# CarrierConnector.net
KiCad netlist of a schematic drawn in Altium Designer
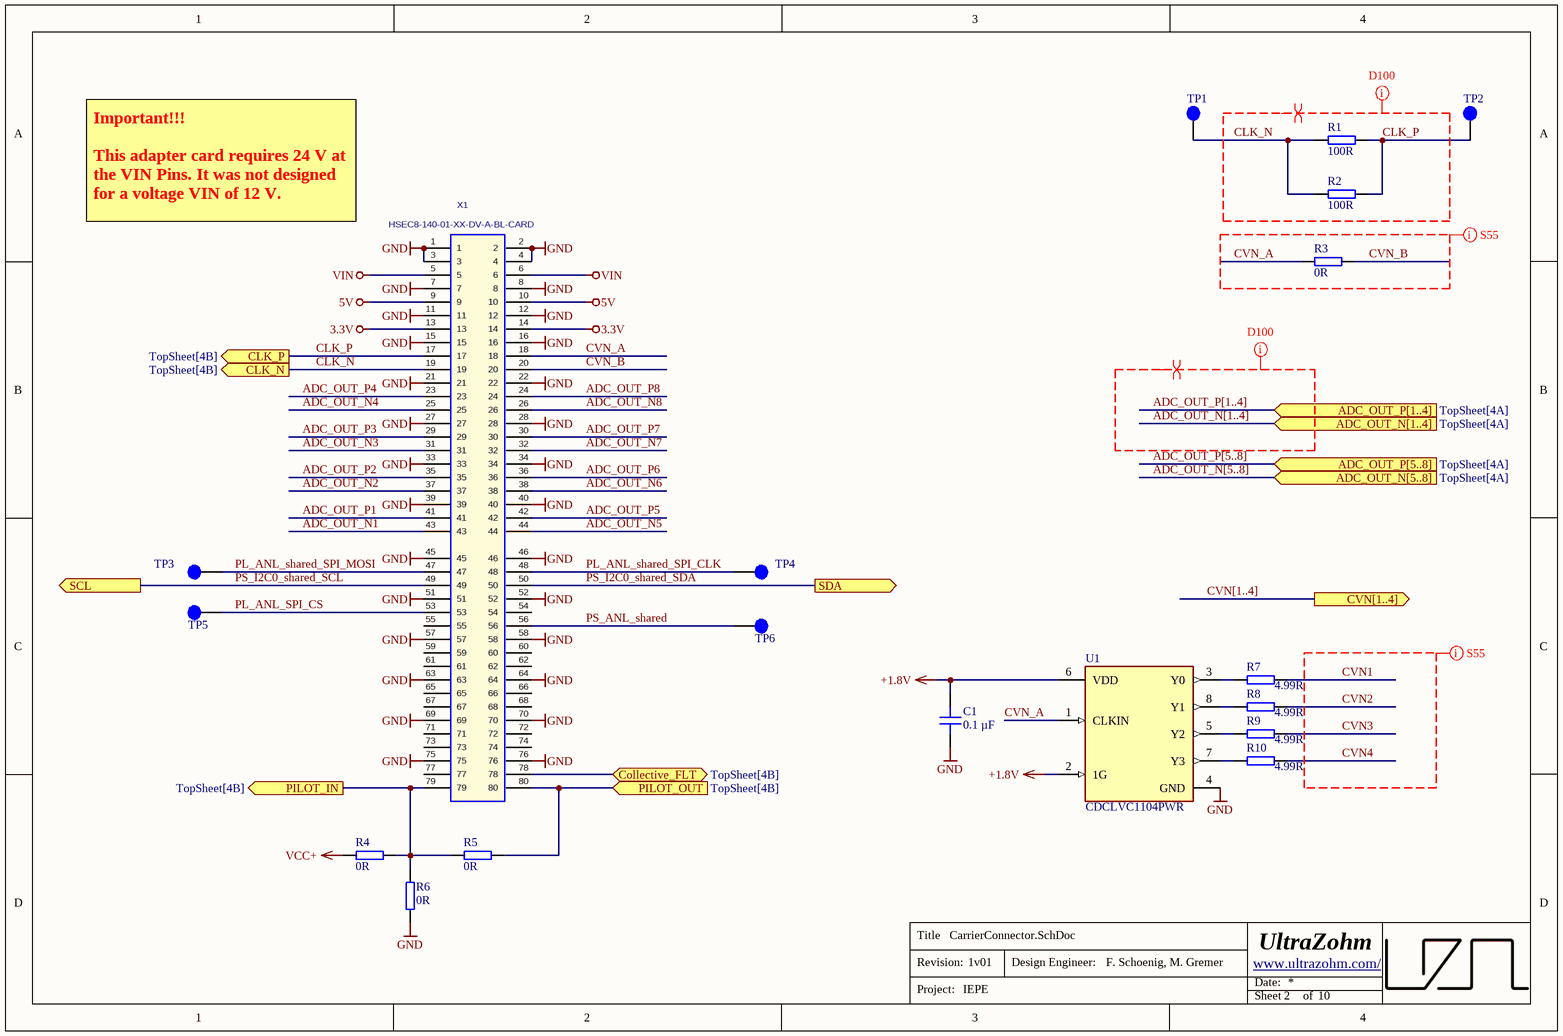
[diagram p0: CarrierConnector.SchDoc]

(export (version "E")
  (design (tool "Eeschema 10.0.6"))
  (components
    (comp (ref "C1")
      (value "0.1 µF")
      (footprint "C_0603")
      (description "Capacitor 0603, 50 VDC, 0.1 µF, X7R")
      (fields
        (field (name "MANUFACTURER PART NUMBER") "C0603X104K5RAC7411")
        (field (name "MANUFACTURER") "KEMET")
        (field (name "CREATED FROM") "MGremer")
      )
      (libsource (lib "user") (part "Capacitor"))
    )
    (comp (ref "R1")
      (value "100R")
      (footprint "RES 0603_1608")
      (description "SMD resistor E24 series")
      (fields
        (field (name "MANUFACTURER PART NUMBER") "RK73B1JTTD101J")
        (field (name "MANUFACTURER") "KOA Speer")
        (field (name "CREATED FROM") "MGremer")
      )
      (libsource (lib "elsys_mariadb_lib") (part "Resistor"))
    )
    (comp (ref "R2")
      (value "100R")
      (footprint "RES 0603_1608")
      (description "SMD resistor E24 series")
      (fields
        (field (name "MANUFACTURER PART NUMBER") "RK73B1JTTD101J")
        (field (name "MANUFACTURER") "KOA Speer")
        (field (name "CREATED FROM") "MGremer")
      )
      (libsource (lib "elsys_mariadb_lib") (part "Resistor"))
    )
    (comp (ref "R3")
      (value "0R")
      (footprint "RES 0603_1608")
      (description "SMD resistor E24 series")
      (fields
        (field (name "MANUFACTURER PART NUMBER") "RC0603JR-070RL")
        (field (name "MANUFACTURER") "YAGEO")
        (field (name "CREATED FROM") "MGremer")
      )
      (libsource (lib "elsys_mariadb_lib") (part "Resistor"))
    )
    (comp (ref "R4")
      (value "0R")
      (footprint "RES 0603_1608")
      (description "SMD resistor E24 series")
      (fields
        (field (name "MANUFACTURER PART NUMBER") "RC0603JR-070RL")
        (field (name "MANUFACTURER") "YAGEO")
        (field (name "CREATED FROM") "MGremer")
      )
      (libsource (lib "elsys_mariadb_lib") (part "Resistor"))
    )
    (comp (ref "R5")
      (value "0R")
      (footprint "RES 0603_1608")
      (description "SMD resistor E24 series")
      (fields
        (field (name "MANUFACTURER PART NUMBER") "RC0603JR-070RL")
        (field (name "MANUFACTURER") "YAGEO")
        (field (name "CREATED FROM") "MGremer")
      )
      (libsource (lib "elsys_mariadb_lib") (part "Resistor"))
    )
    (comp (ref "R6")
      (value "0R")
      (footprint "RES 0603_1608")
      (description "SMD resistor E24 series")
      (fields
        (field (name "MANUFACTURER PART NUMBER") "RC0603JR-070RL")
        (field (name "MANUFACTURER") "YAGEO")
        (field (name "CREATED FROM") "MGremer")
      )
      (libsource (lib "elsys_mariadb_lib") (part "Resistor"))
    )
    (comp (ref "R7")
      (value "4.99R")
      (footprint "RES 0603_1608")
      (description "SMD resistor 1%")
      (fields
        (field (name "MANUFACTURER PART NUMBER") "CRCW06034R99FKEA")
        (field (name "MANUFACTURER") "Vishay / Dale")
        (field (name "CREATED FROM") "MGremer")
      )
      (libsource (lib "elsys_mariadb_lib") (part "Resistor"))
    )
    (comp (ref "R8")
      (value "4.99R")
      (footprint "RES 0603_1608")
      (description "SMD resistor 1%")
      (fields
        (field (name "MANUFACTURER PART NUMBER") "CRCW06034R99FKEA")
        (field (name "MANUFACTURER") "Vishay / Dale")
        (field (name "CREATED FROM") "MGremer")
      )
      (libsource (lib "elsys_mariadb_lib") (part "Resistor"))
    )
    (comp (ref "R9")
      (value "4.99R")
      (footprint "RES 0603_1608")
      (description "SMD resistor 1%")
      (fields
        (field (name "MANUFACTURER PART NUMBER") "CRCW06034R99FKEA")
        (field (name "MANUFACTURER") "Vishay / Dale")
        (field (name "CREATED FROM") "MGremer")
      )
      (libsource (lib "elsys_mariadb_lib") (part "Resistor"))
    )
    (comp (ref "R10")
      (value "4.99R")
      (footprint "RES 0603_1608")
      (description "SMD resistor 1%")
      (fields
        (field (name "MANUFACTURER PART NUMBER") "CRCW06034R99FKEA")
        (field (name "MANUFACTURER") "Vishay / Dale")
        (field (name "CREATED FROM") "MGremer")
      )
      (libsource (lib "elsys_mariadb_lib") (part "Resistor"))
    )
    (comp (ref "TP1")
      (value "-")
      (footprint "TP_1mm")
      (description "Test Point 1 mm")
      (fields (field (name "CREATED") "2018_06_25_AGeiger") (field (name "CREATED FROM") "MGremer"))
      (libsource (lib "user") (part "TP_1mm"))
    )
    (comp (ref "TP2")
      (value "-")
      (footprint "TP_1mm")
      (description "Test Point 1 mm")
      (fields (field (name "CREATED") "2018_06_25_AGeiger") (field (name "CREATED FROM") "MGremer"))
      (libsource (lib "user") (part "TP_1mm"))
    )
    (comp (ref "TP3")
      (value "-")
      (footprint "TP_1mm")
      (description "Test Point 1 mm")
      (fields (field (name "CREATED") "2018_06_25_AGeiger") (field (name "CREATED FROM") "MGremer"))
      (libsource (lib "user") (part "TP_1mm"))
    )
    (comp (ref "TP4")
      (value "-")
      (footprint "TP_1mm")
      (description "Test Point 1 mm")
      (fields (field (name "CREATED") "2018_06_25_AGeiger") (field (name "CREATED FROM") "MGremer"))
      (libsource (lib "user") (part "TP_1mm"))
    )
    (comp (ref "TP5")
      (value "-")
      (footprint "TP_1mm")
      (description "Test Point 1 mm")
      (fields (field (name "CREATED") "2018_06_25_AGeiger") (field (name "CREATED FROM") "MGremer"))
      (libsource (lib "user") (part "TP_1mm"))
    )
    (comp (ref "TP6")
      (value "-")
      (footprint "TP_1mm")
      (description "Test Point 1 mm")
      (fields (field (name "CREATED") "2018_06_25_AGeiger") (field (name "CREATED FROM") "MGremer"))
      (libsource (lib "user") (part "TP_1mm"))
    )
    (comp (ref "U1")
      (value "CDCLVC1104PWR")
      (footprint "FP-PW0008A-MFG")
      (description "High Performance Clock Puffer, 1:4 LVCMOS Fan-out")
      (fields (field (name "MANUFACTURER") "Texas Instruments") (field (name "CREATED FROM") "MGremer"))
      (libsource (lib "user") (part "CDCLVC1104PWR"))
    )
    (comp (ref "X1")
      (value "HSEC8-140-01-XX-DV-A-BL-CARD")
      (footprint "UZohmADC:HSEC8-140-01-XX-DV-A-BL-CARD")
      (description "Mating Card Layout for HSEC8-140-01-XX-DV-A-BL")
      (fields (field (name "MANUFACTURER") "SAMTEC") (field (name "CREATED") "2018_04_23_AGeiger"))
      (libsource (lib "UltraZohm_ADC") (part "HSEC8-140-01-XX-DV-A-BL-CARD"))
    )
  )
  (nets
    (net (code "1") (name "+1.8V") (class "Default")
      (node (ref "C1") (pin "2") (pinfunction "2_2") (pintype "passive"))
      (node (ref "U1") (pin "2") (pinfunction "1G_2") (pintype "input"))
      (node (ref "U1") (pin "6") (pinfunction "VDD_6") (pintype "power_in"))
    )
    (net (code "2") (name "/ADC_OUT_N1") (class "Default")
      (node (ref "X1") (pin "43") (pinfunction "43_43") (pintype "passive"))
    )
    (net (code "3") (name "/ADC_OUT_N2") (class "Default")
      (node (ref "X1") (pin "37") (pinfunction "37_37") (pintype "passive"))
    )
    (net (code "4") (name "/ADC_OUT_N3") (class "Default")
      (node (ref "X1") (pin "31") (pinfunction "31_31") (pintype "passive"))
    )
    (net (code "5") (name "/ADC_OUT_N4") (class "Default")
      (node (ref "X1") (pin "25") (pinfunction "25_25") (pintype "passive"))
    )
    (net (code "6") (name "/ADC_OUT_N5") (class "Default")
      (node (ref "X1") (pin "44") (pinfunction "44_44") (pintype "passive"))
    )
    (net (code "7") (name "/ADC_OUT_N6") (class "Default")
      (node (ref "X1") (pin "38") (pinfunction "38_38") (pintype "passive"))
    )
    (net (code "8") (name "/ADC_OUT_N7") (class "Default")
      (node (ref "X1") (pin "32") (pinfunction "32_32") (pintype "passive"))
    )
    (net (code "9") (name "/ADC_OUT_N8") (class "Default")
      (node (ref "X1") (pin "26") (pinfunction "26_26") (pintype "passive"))
    )
    (net (code "12") (name "/ADC_OUT_P1") (class "Default")
      (node (ref "X1") (pin "41") (pinfunction "41_41") (pintype "passive"))
    )
    (net (code "13") (name "/ADC_OUT_P2") (class "Default")
      (node (ref "X1") (pin "35") (pinfunction "35_35") (pintype "passive"))
    )
    (net (code "14") (name "/ADC_OUT_P3") (class "Default")
      (node (ref "X1") (pin "29") (pinfunction "29_29") (pintype "passive"))
    )
    (net (code "15") (name "/ADC_OUT_P4") (class "Default")
      (node (ref "X1") (pin "23") (pinfunction "23_23") (pintype "passive"))
    )
    (net (code "16") (name "/ADC_OUT_P5") (class "Default")
      (node (ref "X1") (pin "42") (pinfunction "42_42") (pintype "passive"))
    )
    (net (code "17") (name "/ADC_OUT_P6") (class "Default")
      (node (ref "X1") (pin "36") (pinfunction "36_36") (pintype "passive"))
    )
    (net (code "18") (name "/ADC_OUT_P7") (class "Default")
      (node (ref "X1") (pin "30") (pinfunction "30_30") (pintype "passive"))
    )
    (net (code "19") (name "/ADC_OUT_P8") (class "Default")
      (node (ref "X1") (pin "24") (pinfunction "24_24") (pintype "passive"))
    )
    (net (code "22") (name "/CLK_N") (class "Default")
      (node (ref "R1") (pin "1") (pinfunction "1_1") (pintype "passive"))
      (node (ref "R2") (pin "1") (pinfunction "1_1") (pintype "passive"))
      (node (ref "TP1") (pin "1") (pintype "passive"))
      (node (ref "X1") (pin "19") (pinfunction "19_19") (pintype "passive"))
    )
    (net (code "23") (name "/CLK_P") (class "Default")
      (node (ref "R1") (pin "2") (pinfunction "2_2") (pintype "passive"))
      (node (ref "R2") (pin "2") (pinfunction "2_2") (pintype "passive"))
      (node (ref "TP2") (pin "1") (pintype "passive"))
      (node (ref "X1") (pin "17") (pinfunction "17_17") (pintype "passive"))
    )
    (net (code "24") (name "/CVN1") (class "Default")
      (node (ref "R7") (pin "2") (pinfunction "2_2") (pintype "passive"))
    )
    (net (code "25") (name "/CVN2") (class "Default")
      (node (ref "R8") (pin "2") (pinfunction "2_2") (pintype "passive"))
    )
    (net (code "26") (name "/CVN3") (class "Default")
      (node (ref "R9") (pin "2") (pinfunction "2_2") (pintype "passive"))
    )
    (net (code "27") (name "/CVN4") (class "Default")
      (node (ref "R10") (pin "2") (pinfunction "2_2") (pintype "passive"))
    )
    (net (code "29") (name "/CVN_A") (class "Default")
      (node (ref "R3") (pin "1") (pinfunction "1_1") (pintype "passive"))
      (node (ref "U1") (pin "1") (pinfunction "CLKIN_1") (pintype "input"))
      (node (ref "X1") (pin "18") (pinfunction "18_18") (pintype "passive"))
    )
    (net (code "30") (name "/CVN_B") (class "Default")
      (node (ref "R3") (pin "2") (pinfunction "2_2") (pintype "passive"))
      (node (ref "X1") (pin "20") (pinfunction "20_20") (pintype "passive"))
    )
    (net (code "31") (name "/Collective_FLT") (class "Default")
      (node (ref "X1") (pin "78") (pinfunction "78_78") (pintype "passive"))
    )
    (net (code "32") (name "/PILOT_IN") (class "Default")
      (node (ref "R4") (pin "2") (pinfunction "2_2") (pintype "passive"))
      (node (ref "R5") (pin "1") (pinfunction "1_1") (pintype "passive"))
      (node (ref "R6") (pin "2") (pinfunction "2_2") (pintype "passive"))
      (node (ref "X1") (pin "79") (pinfunction "79_79") (pintype "passive"))
    )
    (net (code "33") (name "/PILOT_OUT") (class "Default")
      (node (ref "R5") (pin "2") (pinfunction "2_2") (pintype "passive"))
      (node (ref "X1") (pin "80") (pinfunction "80_80") (pintype "passive"))
    )
    (net (code "34") (name "/PL_ANL_SPI_CS") (class "Default")
      (node (ref "TP5") (pin "1") (pintype "passive"))
      (node (ref "X1") (pin "53") (pinfunction "53_53") (pintype "passive"))
    )
    (net (code "35") (name "/PL_ANL_shared_SPI_CLK") (class "Default")
      (node (ref "TP4") (pin "1") (pintype "passive"))
      (node (ref "X1") (pin "48") (pinfunction "48_48") (pintype "passive"))
    )
    (net (code "36") (name "/PL_ANL_shared_SPI_MOSI") (class "Default")
      (node (ref "TP3") (pin "1") (pintype "passive"))
      (node (ref "X1") (pin "47") (pinfunction "47_47") (pintype "passive"))
    )
    (net (code "37") (name "/PS_ANL_shared") (class "Default")
      (node (ref "TP6") (pin "1") (pintype "passive"))
      (node (ref "X1") (pin "56") (pinfunction "56_56") (pintype "passive"))
    )
    (net (code "38") (name "/PS_I2C0_shared_SCL") (class "Default")
      (node (ref "X1") (pin "49") (pinfunction "49_49") (pintype "passive"))
    )
    (net (code "39") (name "/PS_I2C0_shared_SDA") (class "Default")
      (node (ref "X1") (pin "50") (pinfunction "50_50") (pintype "passive"))
    )
    (net (code "40") (name "3.3V") (class "Default")
      (node (ref "X1") (pin "13") (pinfunction "13_13") (pintype "passive"))
      (node (ref "X1") (pin "14") (pinfunction "14_14") (pintype "passive"))
    )
    (net (code "41") (name "5V") (class "Default")
      (node (ref "X1") (pin "10") (pinfunction "10_10") (pintype "passive"))
      (node (ref "X1") (pin "9") (pinfunction "9_9") (pintype "passive"))
    )
    (net (code "42") (name "GND") (class "Default")
      (node (ref "C1") (pin "1") (pinfunction "1_1") (pintype "passive"))
      (node (ref "R6") (pin "1") (pinfunction "1_1") (pintype "passive"))
      (node (ref "U1") (pin "4") (pinfunction "GND_4") (pintype "power_in"))
      (node (ref "X1") (pin "1") (pinfunction "1_1") (pintype "passive"))
      (node (ref "X1") (pin "11") (pinfunction "11_11") (pintype "passive"))
      (node (ref "X1") (pin "12") (pinfunction "12_12") (pintype "passive"))
      (node (ref "X1") (pin "15") (pinfunction "15_15") (pintype "passive"))
      (node (ref "X1") (pin "16") (pinfunction "16_16") (pintype "passive"))
      (node (ref "X1") (pin "2") (pinfunction "2_2") (pintype "passive"))
      (node (ref "X1") (pin "21") (pinfunction "21_21") (pintype "passive"))
      (node (ref "X1") (pin "22") (pinfunction "22_22") (pintype "passive"))
      (node (ref "X1") (pin "27") (pinfunction "27_27") (pintype "passive"))
      (node (ref "X1") (pin "28") (pinfunction "28_28") (pintype "passive"))
      (node (ref "X1") (pin "3") (pinfunction "3_3") (pintype "passive"))
      (node (ref "X1") (pin "33") (pinfunction "33_33") (pintype "passive"))
      (node (ref "X1") (pin "34") (pinfunction "34_34") (pintype "passive"))
      (node (ref "X1") (pin "39") (pinfunction "39_39") (pintype "passive"))
      (node (ref "X1") (pin "4") (pinfunction "4_4") (pintype "passive"))
      (node (ref "X1") (pin "40") (pinfunction "40_40") (pintype "passive"))
      (node (ref "X1") (pin "45") (pinfunction "45_45") (pintype "passive"))
      (node (ref "X1") (pin "46") (pinfunction "46_46") (pintype "passive"))
      (node (ref "X1") (pin "51") (pinfunction "51_51") (pintype "passive"))
      (node (ref "X1") (pin "52") (pinfunction "52_52") (pintype "passive"))
      (node (ref "X1") (pin "57") (pinfunction "57_57") (pintype "passive"))
      (node (ref "X1") (pin "58") (pinfunction "58_58") (pintype "passive"))
      (node (ref "X1") (pin "63") (pinfunction "63_63") (pintype "passive"))
      (node (ref "X1") (pin "64") (pinfunction "64_64") (pintype "passive"))
      (node (ref "X1") (pin "69") (pinfunction "69_69") (pintype "passive"))
      (node (ref "X1") (pin "7") (pinfunction "7_7") (pintype "passive"))
      (node (ref "X1") (pin "70") (pinfunction "70_70") (pintype "passive"))
      (node (ref "X1") (pin "75") (pinfunction "75_75") (pintype "passive"))
      (node (ref "X1") (pin "76") (pinfunction "76_76") (pintype "passive"))
      (node (ref "X1") (pin "8") (pinfunction "8_8") (pintype "passive"))
    )
    (net (code "43") (name "Net-(U1-Y0)") (class "Default")
      (node (ref "R7") (pin "1") (pinfunction "1_1") (pintype "passive"))
      (node (ref "U1") (pin "3") (pinfunction "Y0_3") (pintype "output"))
    )
    (net (code "44") (name "Net-(U1-Y1)") (class "Default")
      (node (ref "R8") (pin "1") (pinfunction "1_1") (pintype "passive"))
      (node (ref "U1") (pin "8") (pinfunction "Y1_8") (pintype "output"))
    )
    (net (code "45") (name "Net-(U1-Y2)") (class "Default")
      (node (ref "R9") (pin "1") (pinfunction "1_1") (pintype "passive"))
      (node (ref "U1") (pin "5") (pinfunction "Y2_5") (pintype "output"))
    )
    (net (code "46") (name "Net-(U1-Y3)") (class "Default")
      (node (ref "R10") (pin "1") (pinfunction "1_1") (pintype "passive"))
      (node (ref "U1") (pin "7") (pinfunction "Y3_7") (pintype "output"))
    )
    (net (code "47") (name "VCC+") (class "Default")
      (node (ref "R4") (pin "1") (pinfunction "1_1") (pintype "passive"))
    )
    (net (code "48") (name "VIN") (class "Default")
      (node (ref "X1") (pin "5") (pinfunction "5_5") (pintype "passive"))
      (node (ref "X1") (pin "6") (pinfunction "6_6") (pintype "passive"))
    )
    (net (code "49") (name "unconnected-(X1-Pad54)") (class "Default")
      (node (ref "X1") (pin "54") (pinfunction "54_54") (pintype "passive"))
    )
    (net (code "50") (name "unconnected-(X1-Pad55)") (class "Default")
      (node (ref "X1") (pin "55") (pinfunction "55_55") (pintype "passive"))
    )
    (net (code "51") (name "unconnected-(X1-Pad59)") (class "Default")
      (node (ref "X1") (pin "59") (pinfunction "59_59") (pintype "passive"))
    )
    (net (code "52") (name "unconnected-(X1-Pad60)") (class "Default")
      (node (ref "X1") (pin "60") (pinfunction "60_60") (pintype "passive"))
    )
    (net (code "53") (name "unconnected-(X1-Pad61)") (class "Default")
      (node (ref "X1") (pin "61") (pinfunction "61_61") (pintype "passive"))
    )
    (net (code "54") (name "unconnected-(X1-Pad62)") (class "Default")
      (node (ref "X1") (pin "62") (pinfunction "62_62") (pintype "passive"))
    )
    (net (code "55") (name "unconnected-(X1-Pad65)") (class "Default")
      (node (ref "X1") (pin "65") (pinfunction "65_65") (pintype "passive"))
    )
    (net (code "56") (name "unconnected-(X1-Pad66)") (class "Default")
      (node (ref "X1") (pin "66") (pinfunction "66_66") (pintype "passive"))
    )
    (net (code "57") (name "unconnected-(X1-Pad67)") (class "Default")
      (node (ref "X1") (pin "67") (pinfunction "67_67") (pintype "passive"))
    )
    (net (code "58") (name "unconnected-(X1-Pad68)") (class "Default")
      (node (ref "X1") (pin "68") (pinfunction "68_68") (pintype "passive"))
    )
    (net (code "59") (name "unconnected-(X1-Pad71)") (class "Default")
      (node (ref "X1") (pin "71") (pinfunction "71_71") (pintype "passive"))
    )
    (net (code "60") (name "unconnected-(X1-Pad72)") (class "Default")
      (node (ref "X1") (pin "72") (pinfunction "72_72") (pintype "passive"))
    )
    (net (code "61") (name "unconnected-(X1-Pad73)") (class "Default")
      (node (ref "X1") (pin "73") (pinfunction "73_73") (pintype "passive"))
    )
    (net (code "62") (name "unconnected-(X1-Pad74)") (class "Default")
      (node (ref "X1") (pin "74") (pinfunction "74_74") (pintype "passive"))
    )
    (net (code "63") (name "unconnected-(X1-Pad77)") (class "Default")
      (node (ref "X1") (pin "77") (pinfunction "77_77") (pintype "passive"))
    )
  )
)
